# PCB-BI16-4.net
KiCad netlist of a schematic drawn in EAGLE
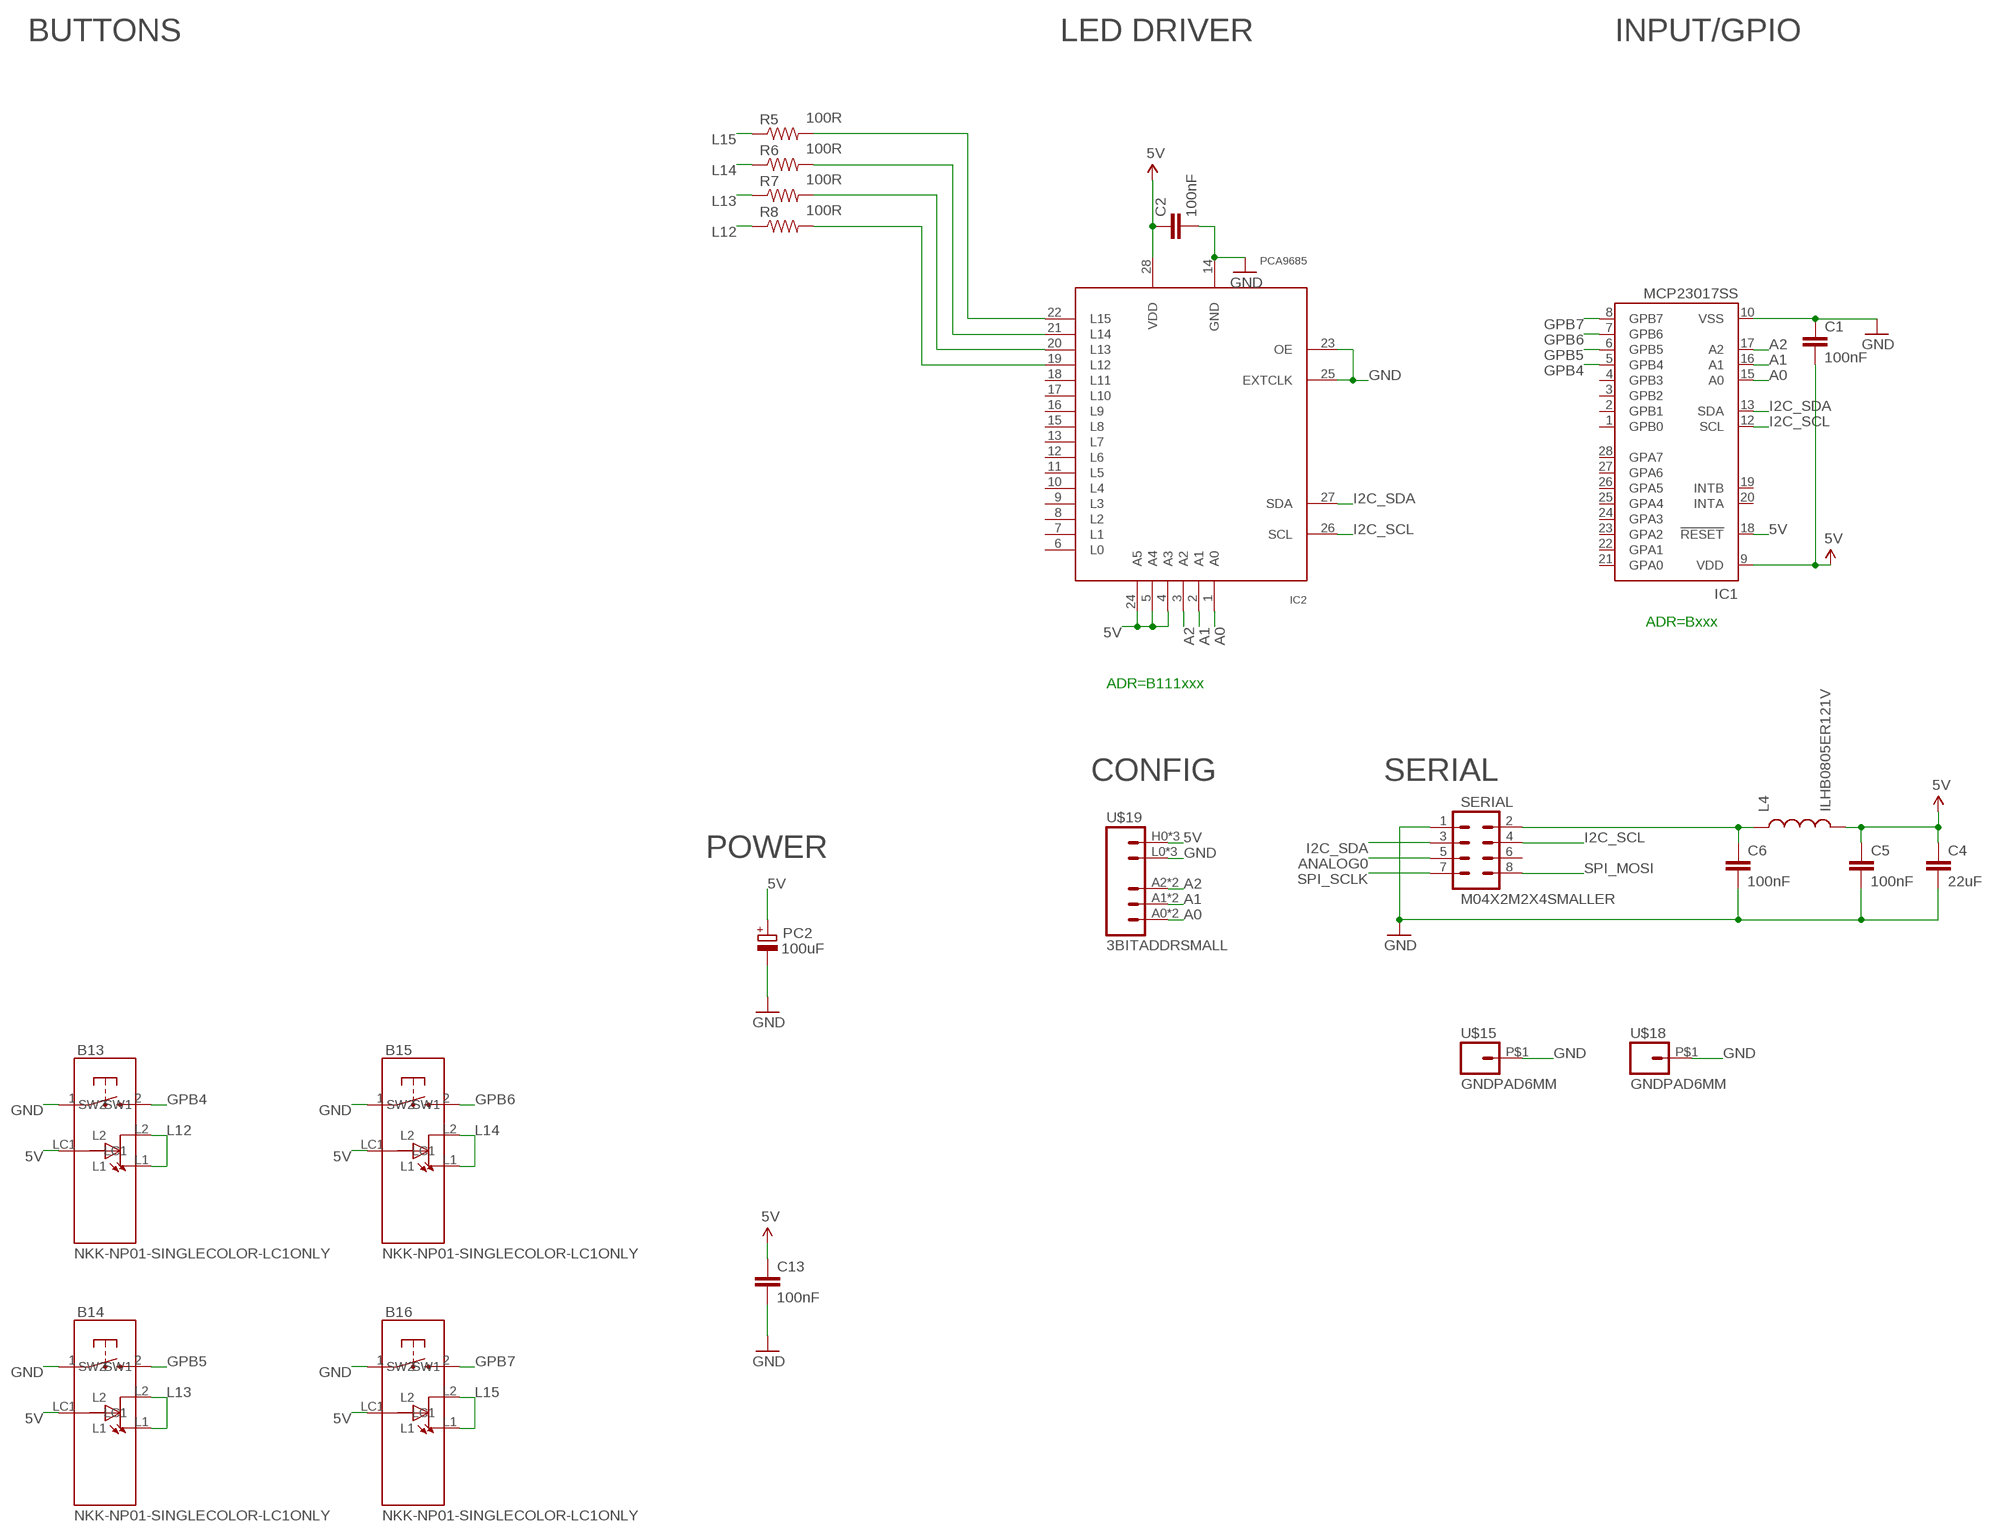
[diagram p0: schematic, sheet 1]

(export (version "E")
  (design (tool "Eeschema 10.0.6"))
  (components
    (comp (ref "B13")
      (value "NKK-NP01-SINGLECOLOR-LC1ONLY")
      (footprint "eagle-import:NKK-NP01_LESSHOLES2")
      (libsource (lib "eagle-import") (part "NKK-NP01-SINGLECOLOR-LC1ONLY"))
    )
    (comp (ref "B14")
      (value "NKK-NP01-SINGLECOLOR-LC1ONLY")
      (footprint "eagle-import:NKK-NP01_LESSHOLES2")
      (libsource (lib "eagle-import") (part "NKK-NP01-SINGLECOLOR-LC1ONLY"))
    )
    (comp (ref "B15")
      (value "NKK-NP01-SINGLECOLOR-LC1ONLY")
      (footprint "eagle-import:NKK-NP01_LESSHOLES2")
      (libsource (lib "eagle-import") (part "NKK-NP01-SINGLECOLOR-LC1ONLY"))
    )
    (comp (ref "B16")
      (value "NKK-NP01-SINGLECOLOR-LC1ONLY")
      (footprint "eagle-import:NKK-NP01_LESSHOLES2")
      (libsource (lib "eagle-import") (part "NKK-NP01-SINGLECOLOR-LC1ONLY"))
    )
    (comp (ref "C1")
      (value "100nF")
      (footprint "eagle-import:0603-CAP")
      (libsource (lib "eagle-import") (part "CAP0603-CAP"))
    )
    (comp (ref "C2")
      (value "100nF")
      (footprint "eagle-import:0603-CAP")
      (libsource (lib "eagle-import") (part "CAP0603-CAP"))
    )
    (comp (ref "C4")
      (value "22uF")
      (footprint "eagle-import:0805")
      (libsource (lib "eagle-import") (part "CAP0805"))
    )
    (comp (ref "C5")
      (value "100nF")
      (footprint "eagle-import:0603-CAP")
      (libsource (lib "eagle-import") (part "CAP0603-CAP"))
    )
    (comp (ref "C6")
      (value "100nF")
      (footprint "eagle-import:0603-CAP")
      (libsource (lib "eagle-import") (part "CAP0603-CAP"))
    )
    (comp (ref "C13")
      (value "100nF")
      (footprint "eagle-import:0603-CAP")
      (libsource (lib "eagle-import") (part "CAP0603-CAP"))
    )
    (comp (ref "IC1")
      (value "MCP23017SS")
      (footprint "eagle-import:SSOP28")
      (fields
        (field (name "MF") "MICROCHIP")
        (field (name "MPN") "MCP23017-E/SS")
        (field (name "MPN_1") "MCP23017-E/SS")
        (field (name "OC_FARNELL") "1467674")
        (field (name "OC_NEWARK") "31K2960")
      )
      (libsource (lib "eagle-import") (part "MCP23017SS"))
    )
    (comp (ref "IC2")
      (value "PCA9685")
      (footprint "eagle-import:TSSOP28")
      (libsource (lib "eagle-import") (part "PCA9685"))
    )
    (comp (ref "L4")
      (value "ILHB0805ER121V")
      (footprint "eagle-import:0805")
      (libsource (lib "eagle-import") (part "INDUCTOR0805"))
    )
    (comp (ref "PC2")
      (value "100uF")
      (footprint "eagle-import:PANASONIC_D")
      (libsource (lib "eagle-import") (part "CPOL-EUD"))
    )
    (comp (ref "R5")
      (value "100R")
      (footprint "eagle-import:0603-RES")
      (libsource (lib "eagle-import") (part "RESISTOR0603-RES"))
    )
    (comp (ref "R6")
      (value "100R")
      (footprint "eagle-import:0603-RES")
      (libsource (lib "eagle-import") (part "RESISTOR0603-RES"))
    )
    (comp (ref "R7")
      (value "100R")
      (footprint "eagle-import:0603-RES")
      (libsource (lib "eagle-import") (part "RESISTOR0603-RES"))
    )
    (comp (ref "R8")
      (value "100R")
      (footprint "eagle-import:0603-RES")
      (libsource (lib "eagle-import") (part "RESISTOR0603-RES"))
    )
    (comp (ref "SERIAL")
      (value "M04X2M2X4SMALLER")
      (footprint "eagle-import:M2X4SMALLER")
      (libsource (lib "eagle-import") (part "M04X2M2X4SMALLER"))
    )
    (comp (ref "U$15")
      (value "GNDPAD6MM")
      (footprint "eagle-import:3.2MMPAD6MM")
      (libsource (lib "eagle-import") (part "GNDPAD6MM"))
    )
    (comp (ref "U$18")
      (value "GNDPAD6MM")
      (footprint "eagle-import:3.2MMPAD6MM")
      (libsource (lib "eagle-import") (part "GNDPAD6MM"))
    )
    (comp (ref "U$19")
      (value "3BITADDRSMALL")
      (footprint "eagle-import:3BITADDR_SMALL")
      (libsource (lib "eagle-import") (part "3BITADDRSMALL"))
    )
  )
  (nets
    (net (code "1") (name "5V") (class "Default")
      (node (ref "B13") (pin "LC1") (pinfunction "LC1_LC1") (pintype "bidirectional"))
      (node (ref "B14") (pin "LC1") (pinfunction "LC1_LC1") (pintype "bidirectional"))
      (node (ref "B15") (pin "LC1") (pinfunction "LC1_LC1") (pintype "bidirectional"))
      (node (ref "B16") (pin "LC1") (pinfunction "LC1_LC1") (pintype "bidirectional"))
      (node (ref "C1") (pin "2") (pinfunction "2_2") (pintype "passive"))
      (node (ref "C13") (pin "1") (pinfunction "1_1") (pintype "passive"))
      (node (ref "C2") (pin "1") (pinfunction "1_1") (pintype "passive"))
      (node (ref "C4") (pin "1") (pinfunction "1_1") (pintype "passive"))
      (node (ref "C5") (pin "1") (pinfunction "1_1") (pintype "passive"))
      (node (ref "IC1") (pin "18") (pinfunction "~{RESET}_18") (pintype "input"))
      (node (ref "IC1") (pin "9") (pinfunction "VDD_9") (pintype "power_in"))
      (node (ref "IC2") (pin "24") (pinfunction "A5_24") (pintype "input"))
      (node (ref "IC2") (pin "28") (pinfunction "VDD_28") (pintype "power_in"))
      (node (ref "IC2") (pin "4") (pinfunction "A3_4") (pintype "input"))
      (node (ref "IC2") (pin "5") (pinfunction "A4_5") (pintype "input"))
      (node (ref "L4") (pin "2") (pinfunction "2_2") (pintype "passive"))
      (node (ref "PC2") (pin "+") (pinfunction "+_+") (pintype "passive"))
      (node (ref "U$19") (pin "H0") (pinfunction "VCC_H0") (pintype "passive"))
      (node (ref "U$19") (pin "H1") (pinfunction "VCC_H1") (pintype "passive"))
      (node (ref "U$19") (pin "H2") (pinfunction "VCC_H2") (pintype "passive"))
    )
    (net (code "2") (name "A0") (class "Default")
      (node (ref "IC1") (pin "15") (pinfunction "A0_15") (pintype "input"))
      (node (ref "IC2") (pin "1") (pinfunction "A0_1") (pintype "input"))
      (node (ref "U$19") (pin "A0") (pinfunction "A0_A0") (pintype "passive"))
      (node (ref "U$19") (pin "AS0") (pinfunction "A0_AS0") (pintype "passive"))
    )
    (net (code "3") (name "A1") (class "Default")
      (node (ref "IC1") (pin "16") (pinfunction "A1_16") (pintype "input"))
      (node (ref "IC2") (pin "2") (pinfunction "A1_2") (pintype "input"))
      (node (ref "U$19") (pin "A1") (pinfunction "A1_A1") (pintype "passive"))
      (node (ref "U$19") (pin "AS1") (pinfunction "A1_AS1") (pintype "passive"))
    )
    (net (code "4") (name "A2") (class "Default")
      (node (ref "IC1") (pin "17") (pinfunction "A2_17") (pintype "input"))
      (node (ref "IC2") (pin "3") (pinfunction "A2_3") (pintype "input"))
      (node (ref "U$19") (pin "A2") (pinfunction "A2_A2") (pintype "passive"))
      (node (ref "U$19") (pin "AS2") (pinfunction "A2_AS2") (pintype "passive"))
    )
    (net (code "5") (name "ANALOG0") (class "Default")
      (node (ref "SERIAL") (pin "5") (pinfunction "5_5") (pintype "passive"))
    )
    (net (code "6") (name "GND") (class "Default")
      (node (ref "B13") (pin "1") (pinfunction "SW1_1") (pintype "bidirectional"))
      (node (ref "B14") (pin "1") (pinfunction "SW1_1") (pintype "bidirectional"))
      (node (ref "B15") (pin "1") (pinfunction "SW1_1") (pintype "bidirectional"))
      (node (ref "B16") (pin "1") (pinfunction "SW1_1") (pintype "bidirectional"))
      (node (ref "C1") (pin "1") (pinfunction "1_1") (pintype "passive"))
      (node (ref "C13") (pin "2") (pinfunction "2_2") (pintype "passive"))
      (node (ref "C2") (pin "2") (pinfunction "2_2") (pintype "passive"))
      (node (ref "C4") (pin "2") (pinfunction "2_2") (pintype "passive"))
      (node (ref "C5") (pin "2") (pinfunction "2_2") (pintype "passive"))
      (node (ref "C6") (pin "2") (pinfunction "2_2") (pintype "passive"))
      (node (ref "IC1") (pin "10") (pinfunction "VSS_10") (pintype "power_in"))
      (node (ref "IC2") (pin "14") (pinfunction "GND_14") (pintype "power_in"))
      (node (ref "IC2") (pin "23") (pinfunction "OE_23") (pintype "input"))
      (node (ref "IC2") (pin "25") (pinfunction "EXTCLK_25") (pintype "input"))
      (node (ref "PC2") (pin "-") (pinfunction "-_-") (pintype "passive"))
      (node (ref "SERIAL") (pin "1") (pinfunction "1_1") (pintype "passive"))
      (node (ref "U$15") (pin "P$1") (pinfunction "1_P$1") (pintype "passive"))
      (node (ref "U$18") (pin "P$1") (pinfunction "1_P$1") (pintype "passive"))
      (node (ref "U$19") (pin "L0") (pinfunction "GND_L0") (pintype "passive"))
      (node (ref "U$19") (pin "L1") (pinfunction "GND_L1") (pintype "passive"))
      (node (ref "U$19") (pin "L2") (pinfunction "GND_L2") (pintype "passive"))
    )
    (net (code "7") (name "GPB4") (class "Default")
      (node (ref "B13") (pin "2") (pinfunction "SW2_2") (pintype "bidirectional"))
      (node (ref "IC1") (pin "5") (pinfunction "GPB4_5") (pintype "bidirectional"))
    )
    (net (code "8") (name "GPB5") (class "Default")
      (node (ref "B14") (pin "2") (pinfunction "SW2_2") (pintype "bidirectional"))
      (node (ref "IC1") (pin "6") (pinfunction "GPB5_6") (pintype "bidirectional"))
    )
    (net (code "9") (name "GPB6") (class "Default")
      (node (ref "B15") (pin "2") (pinfunction "SW2_2") (pintype "bidirectional"))
      (node (ref "IC1") (pin "7") (pinfunction "GPB6_7") (pintype "bidirectional"))
    )
    (net (code "10") (name "GPB7") (class "Default")
      (node (ref "B16") (pin "2") (pinfunction "SW2_2") (pintype "bidirectional"))
      (node (ref "IC1") (pin "8") (pinfunction "GPB7_8") (pintype "bidirectional"))
    )
    (net (code "11") (name "I2C_SCL") (class "Default")
      (node (ref "IC1") (pin "12") (pinfunction "SCL_12") (pintype "input"))
      (node (ref "IC2") (pin "26") (pinfunction "SCL_26") (pintype "input"))
      (node (ref "SERIAL") (pin "4") (pinfunction "4_4") (pintype "passive"))
    )
    (net (code "12") (name "I2C_SDA") (class "Default")
      (node (ref "IC1") (pin "13") (pinfunction "SDA_13") (pintype "bidirectional"))
      (node (ref "IC2") (pin "27") (pinfunction "SDA_27") (pintype "input"))
      (node (ref "SERIAL") (pin "3") (pinfunction "3_3") (pintype "passive"))
    )
    (net (code "13") (name "L12") (class "Default")
      (node (ref "B13") (pin "L1") (pinfunction "L1_L1") (pintype "bidirectional"))
      (node (ref "B13") (pin "L2") (pinfunction "L2_L2") (pintype "bidirectional"))
      (node (ref "R8") (pin "1") (pinfunction "1_1") (pintype "passive"))
    )
    (net (code "14") (name "L13") (class "Default")
      (node (ref "B14") (pin "L1") (pinfunction "L1_L1") (pintype "bidirectional"))
      (node (ref "B14") (pin "L2") (pinfunction "L2_L2") (pintype "bidirectional"))
      (node (ref "R7") (pin "1") (pinfunction "1_1") (pintype "passive"))
    )
    (net (code "15") (name "L14") (class "Default")
      (node (ref "B15") (pin "L1") (pinfunction "L1_L1") (pintype "bidirectional"))
      (node (ref "B15") (pin "L2") (pinfunction "L2_L2") (pintype "bidirectional"))
      (node (ref "R6") (pin "1") (pinfunction "1_1") (pintype "passive"))
    )
    (net (code "16") (name "L15") (class "Default")
      (node (ref "B16") (pin "L1") (pinfunction "L1_L1") (pintype "bidirectional"))
      (node (ref "B16") (pin "L2") (pinfunction "L2_L2") (pintype "bidirectional"))
      (node (ref "R5") (pin "1") (pinfunction "1_1") (pintype "passive"))
    )
    (net (code "17") (name "Net-(C6-Pad1)") (class "Default")
      (node (ref "C6") (pin "1") (pinfunction "1_1") (pintype "passive"))
      (node (ref "L4") (pin "1") (pinfunction "1_1") (pintype "passive"))
      (node (ref "SERIAL") (pin "2") (pinfunction "2_2") (pintype "passive"))
    )
    (net (code "18") (name "Net-(IC2-L12)") (class "Default")
      (node (ref "IC2") (pin "19") (pinfunction "L12_19") (pintype "output"))
      (node (ref "R8") (pin "2") (pinfunction "2_2") (pintype "passive"))
    )
    (net (code "19") (name "Net-(IC2-L13)") (class "Default")
      (node (ref "IC2") (pin "20") (pinfunction "L13_20") (pintype "output"))
      (node (ref "R7") (pin "2") (pinfunction "2_2") (pintype "passive"))
    )
    (net (code "20") (name "Net-(IC2-L14)") (class "Default")
      (node (ref "IC2") (pin "21") (pinfunction "L14_21") (pintype "output"))
      (node (ref "R6") (pin "2") (pinfunction "2_2") (pintype "passive"))
    )
    (net (code "21") (name "Net-(IC2-L15)") (class "Default")
      (node (ref "IC2") (pin "22") (pinfunction "L15_22") (pintype "output"))
      (node (ref "R5") (pin "2") (pinfunction "2_2") (pintype "passive"))
    )
    (net (code "22") (name "SPI_MOSI") (class "Default")
      (node (ref "SERIAL") (pin "8") (pinfunction "8_8") (pintype "passive"))
    )
    (net (code "23") (name "SPI_SCLK") (class "Default")
      (node (ref "SERIAL") (pin "7") (pinfunction "7_7") (pintype "passive"))
    )
    (net (code "24") (name "unconnected-(IC1-GPA0-Pad21)") (class "Default")
      (node (ref "IC1") (pin "21") (pinfunction "GPA0_21") (pintype "bidirectional"))
    )
    (net (code "25") (name "unconnected-(IC1-GPA1-Pad22)") (class "Default")
      (node (ref "IC1") (pin "22") (pinfunction "GPA1_22") (pintype "bidirectional"))
    )
    (net (code "26") (name "unconnected-(IC1-GPA2-Pad23)") (class "Default")
      (node (ref "IC1") (pin "23") (pinfunction "GPA2_23") (pintype "bidirectional"))
    )
    (net (code "27") (name "unconnected-(IC1-GPA3-Pad24)") (class "Default")
      (node (ref "IC1") (pin "24") (pinfunction "GPA3_24") (pintype "bidirectional"))
    )
    (net (code "28") (name "unconnected-(IC1-GPA4-Pad25)") (class "Default")
      (node (ref "IC1") (pin "25") (pinfunction "GPA4_25") (pintype "bidirectional"))
    )
    (net (code "29") (name "unconnected-(IC1-GPA5-Pad26)") (class "Default")
      (node (ref "IC1") (pin "26") (pinfunction "GPA5_26") (pintype "bidirectional"))
    )
    (net (code "30") (name "unconnected-(IC1-GPA6-Pad27)") (class "Default")
      (node (ref "IC1") (pin "27") (pinfunction "GPA6_27") (pintype "bidirectional"))
    )
    (net (code "31") (name "unconnected-(IC1-GPA7-Pad28)") (class "Default")
      (node (ref "IC1") (pin "28") (pinfunction "GPA7_28") (pintype "bidirectional"))
    )
    (net (code "32") (name "unconnected-(IC1-GPB0-Pad1)") (class "Default")
      (node (ref "IC1") (pin "1") (pinfunction "GPB0_1") (pintype "bidirectional"))
    )
    (net (code "33") (name "unconnected-(IC1-GPB1-Pad2)") (class "Default")
      (node (ref "IC1") (pin "2") (pinfunction "GPB1_2") (pintype "bidirectional"))
    )
    (net (code "34") (name "unconnected-(IC1-GPB2-Pad3)") (class "Default")
      (node (ref "IC1") (pin "3") (pinfunction "GPB2_3") (pintype "bidirectional"))
    )
    (net (code "35") (name "unconnected-(IC1-GPB3-Pad4)") (class "Default")
      (node (ref "IC1") (pin "4") (pinfunction "GPB3_4") (pintype "bidirectional"))
    )
    (net (code "36") (name "unconnected-(IC1-INTA-Pad20)") (class "Default")
      (node (ref "IC1") (pin "20") (pinfunction "INTA_20") (pintype "output"))
    )
    (net (code "37") (name "unconnected-(IC1-INTB-Pad19)") (class "Default")
      (node (ref "IC1") (pin "19") (pinfunction "INTB_19") (pintype "output"))
    )
    (net (code "38") (name "unconnected-(IC2-L0-Pad6)") (class "Default")
      (node (ref "IC2") (pin "6") (pinfunction "L0_6") (pintype "output"))
    )
    (net (code "39") (name "unconnected-(IC2-L1-Pad7)") (class "Default")
      (node (ref "IC2") (pin "7") (pinfunction "L1_7") (pintype "output"))
    )
    (net (code "40") (name "unconnected-(IC2-L2-Pad8)") (class "Default")
      (node (ref "IC2") (pin "8") (pinfunction "L2_8") (pintype "output"))
    )
    (net (code "41") (name "unconnected-(IC2-L3-Pad9)") (class "Default")
      (node (ref "IC2") (pin "9") (pinfunction "L3_9") (pintype "output"))
    )
    (net (code "42") (name "unconnected-(IC2-L4-Pad10)") (class "Default")
      (node (ref "IC2") (pin "10") (pinfunction "L4_10") (pintype "output"))
    )
    (net (code "43") (name "unconnected-(IC2-L5-Pad11)") (class "Default")
      (node (ref "IC2") (pin "11") (pinfunction "L5_11") (pintype "output"))
    )
    (net (code "44") (name "unconnected-(IC2-L6-Pad12)") (class "Default")
      (node (ref "IC2") (pin "12") (pinfunction "L6_12") (pintype "output"))
    )
    (net (code "45") (name "unconnected-(IC2-L7-Pad13)") (class "Default")
      (node (ref "IC2") (pin "13") (pinfunction "L7_13") (pintype "output"))
    )
    (net (code "46") (name "unconnected-(IC2-L8-Pad15)") (class "Default")
      (node (ref "IC2") (pin "15") (pinfunction "L8_15") (pintype "output"))
    )
    (net (code "47") (name "unconnected-(IC2-L9-Pad16)") (class "Default")
      (node (ref "IC2") (pin "16") (pinfunction "L9_16") (pintype "output"))
    )
    (net (code "48") (name "unconnected-(IC2-L10-Pad17)") (class "Default")
      (node (ref "IC2") (pin "17") (pinfunction "L10_17") (pintype "output"))
    )
    (net (code "49") (name "unconnected-(IC2-L11-Pad18)") (class "Default")
      (node (ref "IC2") (pin "18") (pinfunction "L11_18") (pintype "output"))
    )
    (net (code "50") (name "unconnected-(SERIAL-Pad6)") (class "Default")
      (node (ref "SERIAL") (pin "6") (pinfunction "6_6") (pintype "passive"))
    )
  )
)
